# greenhousectrl-lab.net
KiCad netlist of a schematic drawn in EAGLE
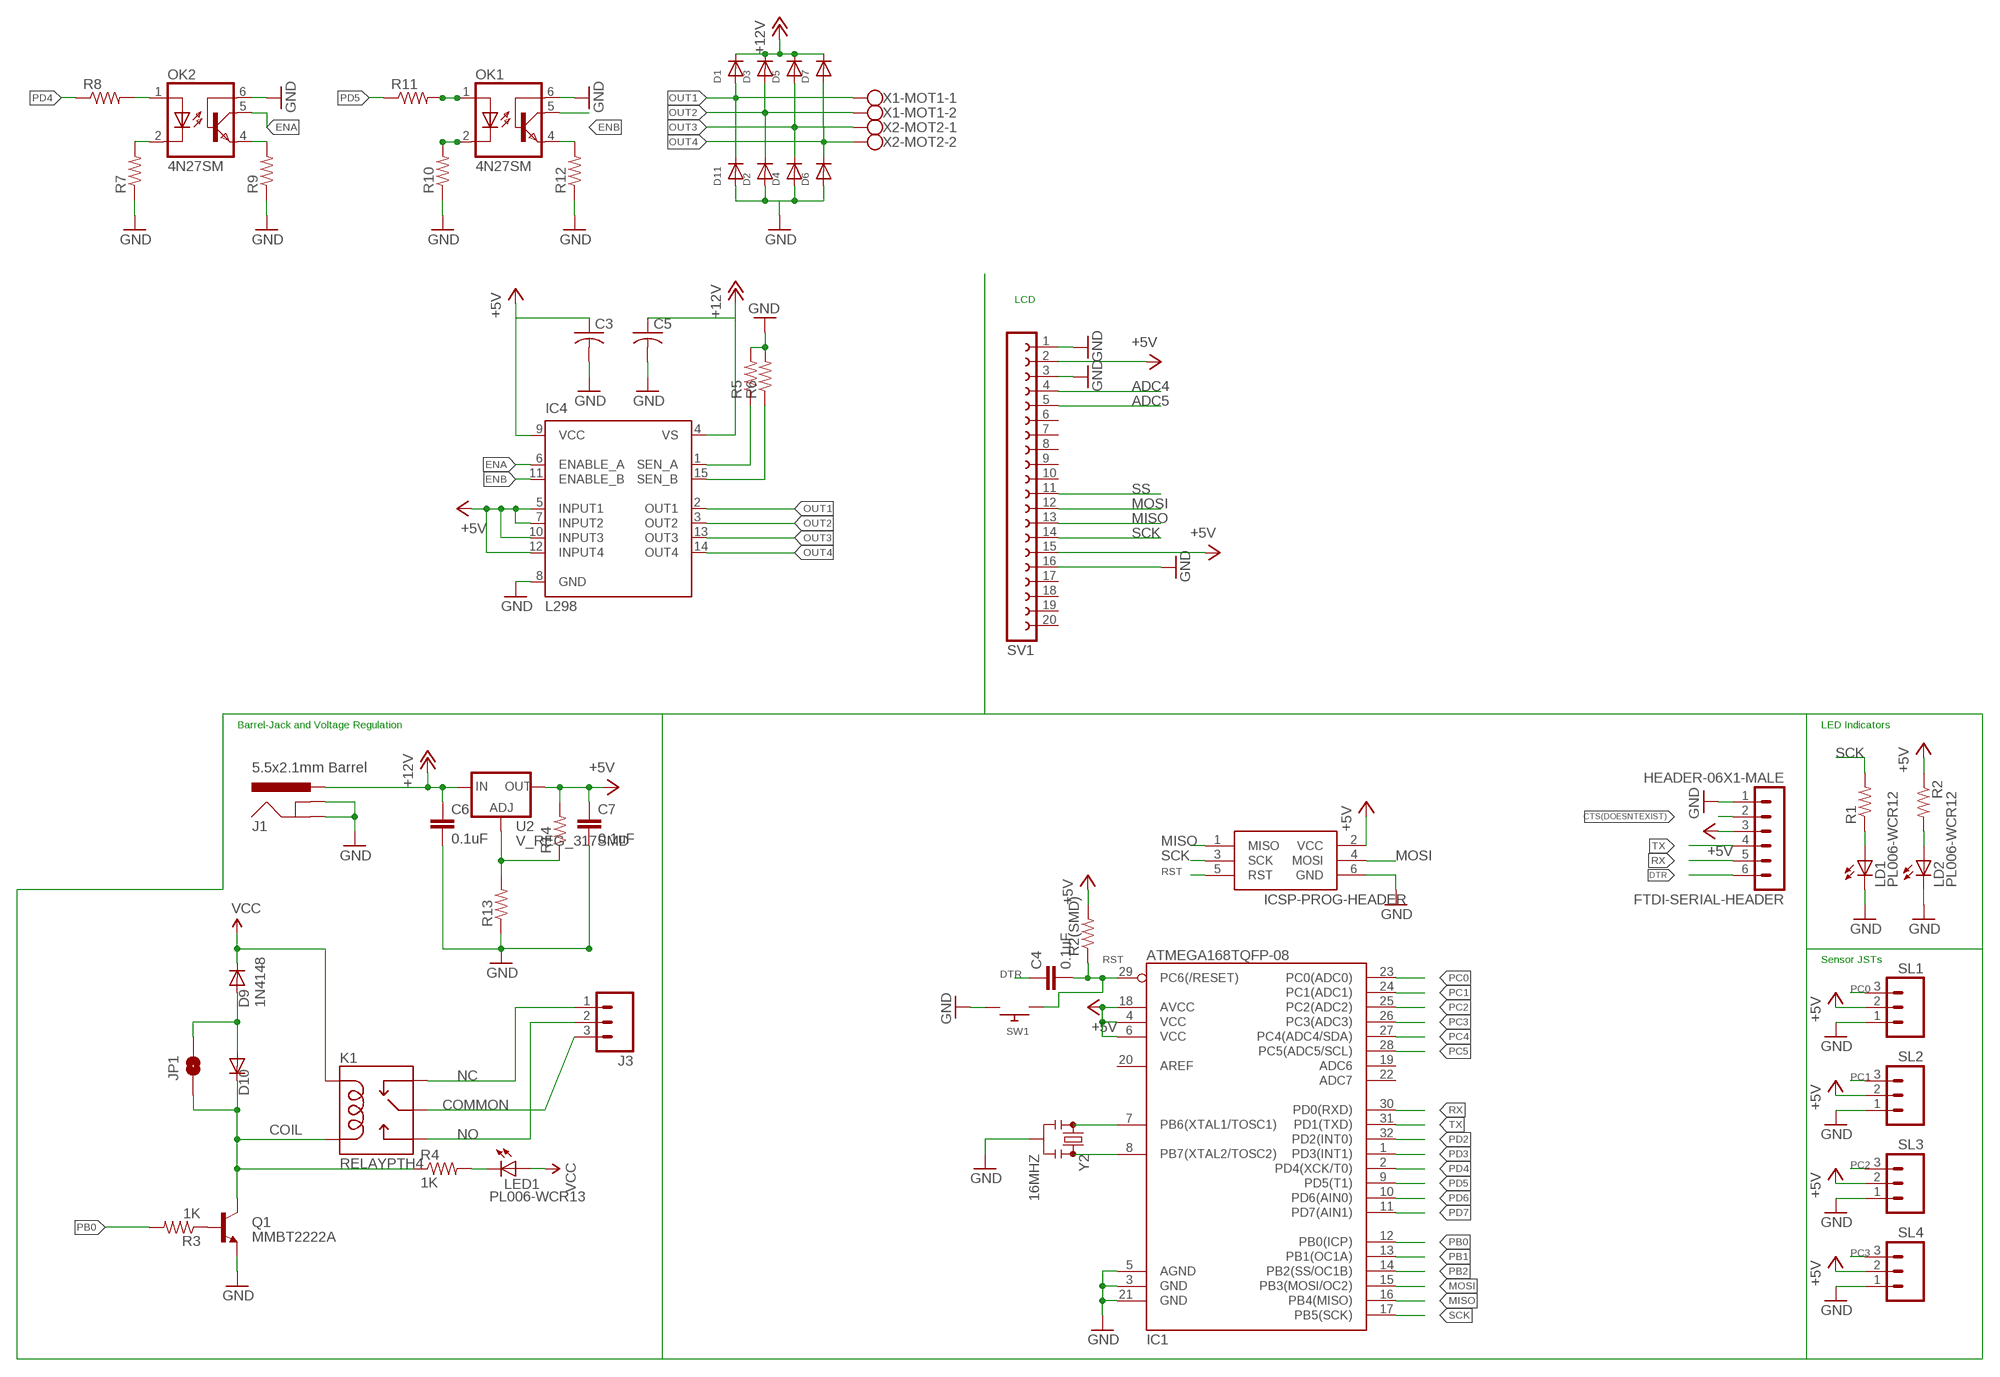
[diagram p0: schematic, sheet 1]

(export (version "E")
  (design (tool "Eeschema 10.0.6"))
  (components
    (comp (ref "C3")
      (value "C-US025-024X044")
      (footprint "eagle-import:C025-024X044")
      (libsource (lib "eagle-import") (part "C-US025-024X044"))
    )
    (comp (ref "C4")
      (value "0.1uF")
      (footprint "eagle-import:0603-CAP")
      (libsource (lib "eagle-import") (part "0.1UF-25V(+80/-20%)(0603)"))
    )
    (comp (ref "C5")
      (value "C-US025-024X044")
      (footprint "eagle-import:C025-024X044")
      (libsource (lib "eagle-import") (part "C-US025-024X044"))
    )
    (comp (ref "C6")
      (value "0.1uF")
      (footprint "eagle-import:0603-CAP")
      (libsource (lib "eagle-import") (part "0.1UF-25V(+80/-20%)(0603)"))
    )
    (comp (ref "C7")
      (value "0.1uF")
      (footprint "eagle-import:0603-CAP")
      (libsource (lib "eagle-import") (part "0.1UF-25V(+80/-20%)(0603)"))
    )
    (comp (ref "D1")
      (value "DIODESOD-523")
      (footprint "eagle-import:SOD-523")
      (libsource (lib "eagle-import") (part "DIODESOD-523"))
    )
    (comp (ref "D2")
      (value "DIODESOD-523")
      (footprint "eagle-import:SOD-523")
      (libsource (lib "eagle-import") (part "DIODESOD-523"))
    )
    (comp (ref "D3")
      (value "DIODESOD-523")
      (footprint "eagle-import:SOD-523")
      (libsource (lib "eagle-import") (part "DIODESOD-523"))
    )
    (comp (ref "D4")
      (value "DIODESOD-523")
      (footprint "eagle-import:SOD-523")
      (libsource (lib "eagle-import") (part "DIODESOD-523"))
    )
    (comp (ref "D5")
      (value "DIODESOD-523")
      (footprint "eagle-import:SOD-523")
      (libsource (lib "eagle-import") (part "DIODESOD-523"))
    )
    (comp (ref "D6")
      (value "DIODESOD-523")
      (footprint "eagle-import:SOD-523")
      (libsource (lib "eagle-import") (part "DIODESOD-523"))
    )
    (comp (ref "D7")
      (value "DIODESOD-523")
      (footprint "eagle-import:SOD-523")
      (libsource (lib "eagle-import") (part "DIODESOD-523"))
    )
    (comp (ref "D9")
      (value "1N4148")
      (footprint "eagle-import:SOD-323F")
      (libsource (lib "eagle-import") (part "DIODESOD-323F"))
    )
    (comp (ref "D10")
      (value "Zener")
      (footprint "eagle-import:SOD-323F")
      (libsource (lib "eagle-import") (part "DIODESOD-323F"))
    )
    (comp (ref "D11")
      (value "DIODESOD-523")
      (footprint "eagle-import:SOD-523")
      (libsource (lib "eagle-import") (part "DIODESOD-523"))
    )
    (comp (ref "FTDI-SERIAL-HEADER")
      (value "HEADER-06X1-MALE")
      (footprint "eagle-import:06X1-PTH")
      (libsource (lib "eagle-import") (part "HEADER-06X1?-MALE"))
    )
    (comp (ref "IC1")
      (value "ATMEGA168TQFP-08")
      (footprint "eagle-import:TQFP32-08")
      (libsource (lib "eagle-import") (part "ATMEGA168TQFP-08"))
    )
    (comp (ref "IC4")
      (value "L298")
      (footprint "eagle-import:MULTIWATT-15")
      (fields (field (name "MPN") "L298N"))
      (libsource (lib "eagle-import") (part "L298"))
    )
    (comp (ref "ICSP-PROG-HEADER")
      (value "AVRISP-6")
      (footprint "eagle-import:AVRISP")
      (libsource (lib "eagle-import") (part "AVRISP-6"))
    )
    (comp (ref "J1")
      (value "5.5x2.1mm Barrel")
      (footprint "eagle-import:POWER_JACK_SMD")
      (libsource (lib "eagle-import") (part "POWER_JACKSMD"))
    )
    (comp (ref "J3")
      (value "M03-SCREW-5MM")
      (footprint "eagle-import:SCREWTERMINAL-5MM-3")
      (libsource (lib "eagle-import") (part "M03-SCREW-5MM"))
    )
    (comp (ref "JP1")
      (value "JUMPER-PAD-2-NOYES_SILK")
      (footprint "eagle-import:PAD-JUMPER-2-NO_YES_SILK")
      (libsource (lib "eagle-import") (part "JUMPER-PAD-2-NOYES_SILK"))
    )
    (comp (ref "K1")
      (value "RELAYPTH4")
      (footprint "eagle-import:RELAY-JZC")
      (libsource (lib "eagle-import") (part "RELAYPTH4"))
    )
    (comp (ref "LD1")
      (value "PL006-WCR12")
      (footprint "eagle-import:SOT23")
      (libsource (lib "eagle-import") (part "PL006-WCR12"))
    )
    (comp (ref "LD2")
      (value "PL006-WCR12")
      (footprint "eagle-import:SOT23")
      (libsource (lib "eagle-import") (part "PL006-WCR12"))
    )
    (comp (ref "LED1")
      (value "PL006-WCR13")
      (footprint "eagle-import:SOT23")
      (fields (field (name "PROD_ID") "DIO-09529"))
      (libsource (lib "eagle-import") (part "PL006-WCR13"))
    )
    (comp (ref "OK1")
      (value "4N27SM")
      (footprint "eagle-import:DIL6-SMD")
      (fields (field (name "MF") "FAIRCHILD SEMICONDUCTOR") (field (name "MPN") "4N27S-M"))
      (libsource (lib "eagle-import") (part "4N?MS27"))
    )
    (comp (ref "OK2")
      (value "4N27SM")
      (footprint "eagle-import:DIL6-SMD")
      (fields (field (name "MF") "FAIRCHILD SEMICONDUCTOR") (field (name "MPN") "4N27S-M"))
      (libsource (lib "eagle-import") (part "4N?MS27"))
    )
    (comp (ref "Q1")
      (value "MMBT2222A")
      (footprint "eagle-import:SOT23-3")
      (libsource (lib "eagle-import") (part "TRANSISTOR_NPNMMBT2222A"))
    )
    (comp (ref "R1")
      (value "R-US_M0805")
      (footprint "eagle-import:M0805")
      (libsource (lib "eagle-import") (part "R-US_M0805"))
    )
    (comp (ref "R2")
      (value "R-US_M0805")
      (footprint "eagle-import:M0805")
      (libsource (lib "eagle-import") (part "R-US_M0805"))
    )
    (comp (ref "R2(SMD)")
      (value "R-US_M0805")
      (footprint "eagle-import:M0805")
      (libsource (lib "eagle-import") (part "R-US_M0805"))
    )
    (comp (ref "R3")
      (value "1K")
      (footprint "eagle-import:M0805")
      (libsource (lib "eagle-import") (part "R-US_M0805"))
    )
    (comp (ref "R4")
      (value "1K")
      (footprint "eagle-import:M0805")
      (libsource (lib "eagle-import") (part "R-US_M0805"))
    )
    (comp (ref "R5")
      (value "R-US_M0805")
      (footprint "eagle-import:M0805")
      (libsource (lib "eagle-import") (part "R-US_M0805"))
    )
    (comp (ref "R6")
      (value "R-US_M0805")
      (footprint "eagle-import:M0805")
      (libsource (lib "eagle-import") (part "R-US_M0805"))
    )
    (comp (ref "R7")
      (value "R-US_M0805")
      (footprint "eagle-import:M0805")
      (libsource (lib "eagle-import") (part "R-US_M0805"))
    )
    (comp (ref "R8")
      (value "R-US_M0805")
      (footprint "eagle-import:M0805")
      (libsource (lib "eagle-import") (part "R-US_M0805"))
    )
    (comp (ref "R9")
      (value "R-US_M0805")
      (footprint "eagle-import:M0805")
      (libsource (lib "eagle-import") (part "R-US_M0805"))
    )
    (comp (ref "R10")
      (value "R-US_M0805")
      (footprint "eagle-import:M0805")
      (libsource (lib "eagle-import") (part "R-US_M0805"))
    )
    (comp (ref "R11")
      (value "R-US_M0805")
      (footprint "eagle-import:M0805")
      (libsource (lib "eagle-import") (part "R-US_M0805"))
    )
    (comp (ref "R12")
      (value "R-US_M0805")
      (footprint "eagle-import:M0805")
      (libsource (lib "eagle-import") (part "R-US_M0805"))
    )
    (comp (ref "R13")
      (value "RESISTOR0402")
      (footprint "eagle-import:0402-RES")
      (libsource (lib "eagle-import") (part "RESISTOR0402"))
    )
    (comp (ref "R14")
      (value "RESISTOR0402")
      (footprint "eagle-import:0402-RES")
      (libsource (lib "eagle-import") (part "RESISTOR0402"))
    )
    (comp (ref "SL1")
      (value "M03")
      (footprint "eagle-import:03P")
      (libsource (lib "eagle-import") (part "M03"))
    )
    (comp (ref "SL2")
      (value "M03")
      (footprint "eagle-import:03P")
      (libsource (lib "eagle-import") (part "M03"))
    )
    (comp (ref "SL3")
      (value "M03")
      (footprint "eagle-import:03P")
      (libsource (lib "eagle-import") (part "M03"))
    )
    (comp (ref "SL4")
      (value "M03")
      (footprint "eagle-import:03P")
      (libsource (lib "eagle-import") (part "M03"))
    )
    (comp (ref "SV1")
      (value "FE20-1")
      (footprint "eagle-import:FE20")
      (libsource (lib "eagle-import") (part "FE20-1"))
    )
    (comp (ref "SW1")
      (value "SWITCH_PUSHBUTTONC&K_KSS")
      (footprint "eagle-import:BTN_CK_KSS")
      (libsource (lib "eagle-import") (part "SWITCH_PUSHBUTTONC&K_KSS"))
    )
    (comp (ref "U2")
      (value "V_REG_317SMD")
      (footprint "eagle-import:SOT223")
      (libsource (lib "eagle-import") (part "V_REG_317SMD"))
    )
    (comp (ref "X1-MOT1")
      (value "W237-102")
      (footprint "eagle-import:W237-102")
      (fields (field (name "MPN") "237-102"))
      (libsource (lib "eagle-import") (part "W237-102"))
    )
    (comp (ref "X2-MOT2")
      (value "W237-102")
      (footprint "eagle-import:W237-102")
      (fields (field (name "MPN") "237-102"))
      (libsource (lib "eagle-import") (part "W237-102"))
    )
    (comp (ref "Y2")
      (value "16MHZ")
      (footprint "eagle-import:RESONATOR-SMD")
      (libsource (lib "eagle-import") (part "RESONATOR16MHZ"))
    )
  )
  (nets
    (net (code "1") (name "+5V") (class "Default")
      (node (ref "C3") (pin "1") (pinfunction "1_1") (pintype "passive"))
      (node (ref "C7") (pin "1") (pinfunction "1_1") (pintype "passive"))
      (node (ref "FTDI-SERIAL-HEADER") (pin "3") (pinfunction "3_3") (pintype "passive"))
      (node (ref "IC1") (pin "18") (pinfunction "AVCC_18") (pintype "bidirectional"))
      (node (ref "IC1") (pin "4") (pinfunction "VCC_4") (pintype "bidirectional"))
      (node (ref "IC1") (pin "6") (pinfunction "VCC_6") (pintype "bidirectional"))
      (node (ref "IC4") (pin "10") (pinfunction "INPUT3_10") (pintype "input"))
      (node (ref "IC4") (pin "12") (pinfunction "INPUT4_12") (pintype "input"))
      (node (ref "IC4") (pin "5") (pinfunction "INPUT1_5") (pintype "input"))
      (node (ref "IC4") (pin "7") (pinfunction "INPUT2_7") (pintype "input"))
      (node (ref "IC4") (pin "9") (pinfunction "VCC_9") (pintype "power_in"))
      (node (ref "ICSP-PROG-HEADER") (pin "2") (pinfunction "VCC_2") (pintype "power_in"))
      (node (ref "R14") (pin "2") (pinfunction "2_2") (pintype "passive"))
      (node (ref "R2") (pin "1") (pinfunction "1_1") (pintype "passive"))
      (node (ref "R2(SMD)") (pin "2") (pinfunction "2_2") (pintype "passive"))
      (node (ref "SL1") (pin "2") (pinfunction "2_2") (pintype "passive"))
      (node (ref "SL2") (pin "2") (pinfunction "2_2") (pintype "passive"))
      (node (ref "SL3") (pin "2") (pinfunction "2_2") (pintype "passive"))
      (node (ref "SL4") (pin "2") (pinfunction "2_2") (pintype "passive"))
      (node (ref "SV1") (pin "15") (pinfunction "15_15") (pintype "passive"))
      (node (ref "SV1") (pin "2") (pinfunction "2_2") (pintype "passive"))
      (node (ref "U2") (pin "2") (pinfunction "OUT_2") (pintype "output"))
    )
    (net (code "2") (name "+12V") (class "Default")
      (node (ref "C5") (pin "1") (pinfunction "1_1") (pintype "passive"))
      (node (ref "C6") (pin "1") (pinfunction "1_1") (pintype "passive"))
      (node (ref "D1") (pin "K") (pinfunction "C_K") (pintype "passive"))
      (node (ref "D3") (pin "K") (pinfunction "C_K") (pintype "passive"))
      (node (ref "D5") (pin "K") (pinfunction "C_K") (pintype "passive"))
      (node (ref "D7") (pin "K") (pinfunction "C_K") (pintype "passive"))
      (node (ref "IC4") (pin "4") (pinfunction "VS_4") (pintype "power_in"))
      (node (ref "J1") (pin "VIN0") (pinfunction "PWR_VIN0") (pintype "bidirectional"))
      (node (ref "U2") (pin "3") (pinfunction "IN_3") (pintype "input"))
    )
    (net (code "3") (name "/ADC4") (class "Default")
      (node (ref "SV1") (pin "4") (pinfunction "4_4") (pintype "passive"))
    )
    (net (code "4") (name "/ADC5") (class "Default")
      (node (ref "SV1") (pin "5") (pinfunction "5_5") (pintype "passive"))
    )
    (net (code "5") (name "/COIL") (class "Default")
      (node (ref "D10") (pin "C") (pinfunction "C_C") (pintype "passive"))
      (node (ref "JP1") (pin "1") (pinfunction "1_1") (pintype "passive"))
      (node (ref "K1") (pin "1") (pinfunction "COIL2_1") (pintype "bidirectional"))
      (node (ref "Q1") (pin "3") (pinfunction "C_3") (pintype "passive"))
      (node (ref "R4") (pin "1") (pinfunction "1_1") (pintype "passive"))
    )
    (net (code "6") (name "/COMMON") (class "Default")
      (node (ref "J3") (pin "3") (pinfunction "3_3") (pintype "passive"))
      (node (ref "K1") (pin "4") (pinfunction "MAIN_4") (pintype "bidirectional"))
    )
    (net (code "7") (name "/NC") (class "Default")
      (node (ref "J3") (pin "1") (pinfunction "1_1") (pintype "passive"))
      (node (ref "K1") (pin "2") (pinfunction "NC_2") (pintype "bidirectional"))
    )
    (net (code "8") (name "/NO") (class "Default")
      (node (ref "J3") (pin "2") (pinfunction "2_2") (pintype "passive"))
      (node (ref "K1") (pin "3") (pinfunction "NO_3") (pintype "bidirectional"))
    )
    (net (code "9") (name "/RST") (class "Default")
      (node (ref "C4") (pin "2") (pinfunction "2_2") (pintype "passive"))
      (node (ref "IC1") (pin "29") (pinfunction "PC6(/RESET)_29") (pintype "bidirectional"))
      (node (ref "ICSP-PROG-HEADER") (pin "5") (pinfunction "RST_5") (pintype "output"))
      (node (ref "R2(SMD)") (pin "1") (pinfunction "1_1") (pintype "passive"))
      (node (ref "SW1") (pin "P$1") (pinfunction "P$1_P$1") (pintype "passive"))
    )
    (net (code "10") (name "/SS") (class "Default")
      (node (ref "SV1") (pin "11") (pinfunction "11_11") (pintype "passive"))
    )
    (net (code "11") (name "CTS(DOESNTEXIST)") (class "Default")
      (node (ref "FTDI-SERIAL-HEADER") (pin "2") (pinfunction "2_2") (pintype "passive"))
    )
    (net (code "12") (name "DTR") (class "Default")
      (node (ref "C4") (pin "1") (pinfunction "1_1") (pintype "passive"))
      (node (ref "FTDI-SERIAL-HEADER") (pin "6") (pinfunction "6_6") (pintype "passive"))
    )
    (net (code "13") (name "ENA") (class "Default")
      (node (ref "IC4") (pin "6") (pinfunction "ENABLE_A_6") (pintype "input"))
      (node (ref "OK2") (pin "5") (pinfunction "COL_5") (pintype "passive"))
    )
    (net (code "14") (name "ENB") (class "Default")
      (node (ref "IC4") (pin "11") (pinfunction "ENABLE_B_11") (pintype "input"))
      (node (ref "OK1") (pin "5") (pinfunction "COL_5") (pintype "passive"))
    )
    (net (code "15") (name "GND") (class "Default")
      (node (ref "C3") (pin "2") (pinfunction "2_2") (pintype "passive"))
      (node (ref "C5") (pin "2") (pinfunction "2_2") (pintype "passive"))
      (node (ref "C6") (pin "2") (pinfunction "2_2") (pintype "passive"))
      (node (ref "C7") (pin "2") (pinfunction "2_2") (pintype "passive"))
      (node (ref "D11") (pin "A") (pinfunction "A_A") (pintype "passive"))
      (node (ref "D2") (pin "A") (pinfunction "A_A") (pintype "passive"))
      (node (ref "D4") (pin "A") (pinfunction "A_A") (pintype "passive"))
      (node (ref "D6") (pin "A") (pinfunction "A_A") (pintype "passive"))
      (node (ref "FTDI-SERIAL-HEADER") (pin "1") (pinfunction "1_1") (pintype "passive"))
      (node (ref "IC1") (pin "21") (pinfunction "GND_21") (pintype "bidirectional"))
      (node (ref "IC1") (pin "3") (pinfunction "GND_3") (pintype "bidirectional"))
      (node (ref "IC1") (pin "5") (pinfunction "AGND_5") (pintype "bidirectional"))
      (node (ref "IC4") (pin "8") (pinfunction "GND_8") (pintype "power_in"))
      (node (ref "ICSP-PROG-HEADER") (pin "6") (pinfunction "GND_6") (pintype "power_in"))
      (node (ref "J1") (pin "GND") (pinfunction "GNDBREAK_GND") (pintype "bidirectional"))
      (node (ref "J1") (pin "P$4") (pinfunction "GND_P$4") (pintype "bidirectional"))
      (node (ref "LD1") (pin "3") (pinfunction "C_3") (pintype "passive"))
      (node (ref "LD2") (pin "3") (pinfunction "C_3") (pintype "passive"))
      (node (ref "OK1") (pin "6") (pinfunction "BAS_6") (pintype "passive"))
      (node (ref "OK2") (pin "6") (pinfunction "BAS_6") (pintype "passive"))
      (node (ref "Q1") (pin "2") (pinfunction "E_2") (pintype "passive"))
      (node (ref "R10") (pin "1") (pinfunction "1_1") (pintype "passive"))
      (node (ref "R12") (pin "1") (pinfunction "1_1") (pintype "passive"))
      (node (ref "R13") (pin "1") (pinfunction "1_1") (pintype "passive"))
      (node (ref "R5") (pin "2") (pinfunction "2_2") (pintype "passive"))
      (node (ref "R6") (pin "2") (pinfunction "2_2") (pintype "passive"))
      (node (ref "R7") (pin "1") (pinfunction "1_1") (pintype "passive"))
      (node (ref "R9") (pin "1") (pinfunction "1_1") (pintype "passive"))
      (node (ref "SL1") (pin "1") (pinfunction "1_1") (pintype "passive"))
      (node (ref "SL2") (pin "1") (pinfunction "1_1") (pintype "passive"))
      (node (ref "SL3") (pin "1") (pinfunction "1_1") (pintype "passive"))
      (node (ref "SL4") (pin "1") (pinfunction "1_1") (pintype "passive"))
      (node (ref "SV1") (pin "1") (pinfunction "1_1") (pintype "passive"))
      (node (ref "SV1") (pin "16") (pinfunction "16_16") (pintype "passive"))
      (node (ref "SV1") (pin "3") (pinfunction "3_3") (pintype "passive"))
      (node (ref "SW1") (pin "P$2") (pinfunction "P$2_P$2") (pintype "passive"))
      (node (ref "Y2") (pin "2") (pinfunction "2_2") (pintype "passive"))
    )
    (net (code "16") (name "MISO") (class "Default")
      (node (ref "IC1") (pin "16") (pinfunction "PB4(MISO)_16") (pintype "bidirectional"))
      (node (ref "ICSP-PROG-HEADER") (pin "1") (pinfunction "MISO_1") (pintype "input"))
      (node (ref "SV1") (pin "13") (pinfunction "13_13") (pintype "passive"))
    )
    (net (code "17") (name "MOSI") (class "Default")
      (node (ref "IC1") (pin "15") (pinfunction "PB3(MOSI/OC2)_15") (pintype "bidirectional"))
      (node (ref "ICSP-PROG-HEADER") (pin "4") (pinfunction "MOSI_4") (pintype "output"))
      (node (ref "SV1") (pin "12") (pinfunction "12_12") (pintype "passive"))
    )
    (net (code "18") (name "Net-(D10-PadA)") (class "Default")
      (node (ref "D10") (pin "A") (pinfunction "A_A") (pintype "passive"))
      (node (ref "D9") (pin "A") (pinfunction "A_A") (pintype "passive"))
      (node (ref "JP1") (pin "2") (pinfunction "2_2") (pintype "passive"))
    )
    (net (code "19") (name "Net-(IC1-PB6(XTAL1{slash}TOSC1))") (class "Default")
      (node (ref "IC1") (pin "7") (pinfunction "PB6(XTAL1/TOSC1)_7") (pintype "bidirectional"))
      (node (ref "Y2") (pin "1") (pinfunction "1_1") (pintype "passive"))
    )
    (net (code "20") (name "Net-(IC1-PB7(XTAL2{slash}TOSC2))") (class "Default")
      (node (ref "IC1") (pin "8") (pinfunction "PB7(XTAL2/TOSC2)_8") (pintype "bidirectional"))
      (node (ref "Y2") (pin "3") (pinfunction "3_3") (pintype "passive"))
    )
    (net (code "21") (name "Net-(IC4-SEN_A)") (class "Default")
      (node (ref "IC4") (pin "1") (pinfunction "SEN_A_1") (pintype "input"))
      (node (ref "R5") (pin "1") (pinfunction "1_1") (pintype "passive"))
    )
    (net (code "22") (name "Net-(IC4-SEN_B)") (class "Default")
      (node (ref "IC4") (pin "15") (pinfunction "SEN_B_15") (pintype "input"))
      (node (ref "R6") (pin "1") (pinfunction "1_1") (pintype "passive"))
    )
    (net (code "23") (name "Net-(LD1-A)") (class "Default")
      (node (ref "LD1") (pin "1") (pinfunction "A_1") (pintype "passive"))
      (node (ref "R1") (pin "1") (pinfunction "1_1") (pintype "passive"))
    )
    (net (code "24") (name "Net-(LD2-A)") (class "Default")
      (node (ref "LD2") (pin "1") (pinfunction "A_1") (pintype "passive"))
      (node (ref "R2") (pin "2") (pinfunction "2_2") (pintype "passive"))
    )
    (net (code "25") (name "Net-(LED1-C)") (class "Default")
      (node (ref "LED1") (pin "3") (pinfunction "C_3") (pintype "passive"))
      (node (ref "R4") (pin "2") (pinfunction "2_2") (pintype "passive"))
    )
    (net (code "26") (name "Net-(OK1-A)") (class "Default")
      (node (ref "OK1") (pin "1") (pinfunction "A_1") (pintype "passive"))
      (node (ref "R11") (pin "2") (pinfunction "2_2") (pintype "passive"))
    )
    (net (code "27") (name "Net-(OK1-C)") (class "Default")
      (node (ref "OK1") (pin "2") (pinfunction "C_2") (pintype "passive"))
      (node (ref "R10") (pin "2") (pinfunction "2_2") (pintype "passive"))
    )
    (net (code "28") (name "Net-(OK1-EMI)") (class "Default")
      (node (ref "OK1") (pin "4") (pinfunction "EMI_4") (pintype "passive"))
      (node (ref "R12") (pin "2") (pinfunction "2_2") (pintype "passive"))
    )
    (net (code "29") (name "Net-(OK2-A)") (class "Default")
      (node (ref "OK2") (pin "1") (pinfunction "A_1") (pintype "passive"))
      (node (ref "R8") (pin "2") (pinfunction "2_2") (pintype "passive"))
    )
    (net (code "30") (name "Net-(OK2-C)") (class "Default")
      (node (ref "OK2") (pin "2") (pinfunction "C_2") (pintype "passive"))
      (node (ref "R7") (pin "2") (pinfunction "2_2") (pintype "passive"))
    )
    (net (code "31") (name "Net-(OK2-EMI)") (class "Default")
      (node (ref "OK2") (pin "4") (pinfunction "EMI_4") (pintype "passive"))
      (node (ref "R9") (pin "2") (pinfunction "2_2") (pintype "passive"))
    )
    (net (code "32") (name "Net-(Q1-B)") (class "Default")
      (node (ref "Q1") (pin "1") (pinfunction "B_1") (pintype "passive"))
      (node (ref "R3") (pin "1") (pinfunction "1_1") (pintype "passive"))
    )
    (net (code "33") (name "Net-(U2-ADJ)") (class "Default")
      (node (ref "R13") (pin "2") (pinfunction "2_2") (pintype "passive"))
      (node (ref "R14") (pin "1") (pinfunction "1_1") (pintype "passive"))
      (node (ref "U2") (pin "1") (pinfunction "ADJ_1") (pintype "input"))
    )
    (net (code "34") (name "OUT1") (class "Default")
      (node (ref "D1") (pin "A") (pinfunction "A_A") (pintype "passive"))
      (node (ref "D11") (pin "K") (pinfunction "C_K") (pintype "passive"))
      (node (ref "IC4") (pin "2") (pinfunction "OUT1_2") (pintype "output"))
      (node (ref "X1-MOT1") (pin "1") (pinfunction "KL_1") (pintype "passive"))
    )
    (net (code "35") (name "OUT2") (class "Default")
      (node (ref "D2") (pin "K") (pinfunction "C_K") (pintype "passive"))
      (node (ref "D3") (pin "A") (pinfunction "A_A") (pintype "passive"))
      (node (ref "IC4") (pin "3") (pinfunction "OUT2_3") (pintype "output"))
      (node (ref "X1-MOT1") (pin "2") (pinfunction "KL_2") (pintype "passive"))
    )
    (net (code "36") (name "OUT3") (class "Default")
      (node (ref "D4") (pin "K") (pinfunction "C_K") (pintype "passive"))
      (node (ref "D5") (pin "A") (pinfunction "A_A") (pintype "passive"))
      (node (ref "IC4") (pin "13") (pinfunction "OUT3_13") (pintype "output"))
      (node (ref "X2-MOT2") (pin "1") (pinfunction "KL_1") (pintype "passive"))
    )
    (net (code "37") (name "OUT4") (class "Default")
      (node (ref "D6") (pin "K") (pinfunction "C_K") (pintype "passive"))
      (node (ref "D7") (pin "A") (pinfunction "A_A") (pintype "passive"))
      (node (ref "IC4") (pin "14") (pinfunction "OUT4_14") (pintype "output"))
      (node (ref "X2-MOT2") (pin "2") (pinfunction "KL_2") (pintype "passive"))
    )
    (net (code "38") (name "PB0") (class "Default")
      (node (ref "IC1") (pin "12") (pinfunction "PB0(ICP)_12") (pintype "bidirectional"))
      (node (ref "R3") (pin "2") (pinfunction "2_2") (pintype "passive"))
    )
    (net (code "39") (name "PB1") (class "Default")
      (node (ref "IC1") (pin "13") (pinfunction "PB1(OC1A)_13") (pintype "bidirectional"))
    )
    (net (code "40") (name "PB2") (class "Default")
      (node (ref "IC1") (pin "14") (pinfunction "PB2(SS/OC1B)_14") (pintype "bidirectional"))
    )
    (net (code "41") (name "PC0") (class "Default")
      (node (ref "IC1") (pin "23") (pinfunction "PC0(ADC0)_23") (pintype "bidirectional"))
      (node (ref "SL1") (pin "3") (pinfunction "3_3") (pintype "passive"))
    )
    (net (code "42") (name "PC1") (class "Default")
      (node (ref "IC1") (pin "24") (pinfunction "PC1(ADC1)_24") (pintype "bidirectional"))
      (node (ref "SL2") (pin "3") (pinfunction "3_3") (pintype "passive"))
    )
    (net (code "43") (name "PC2") (class "Default")
      (node (ref "IC1") (pin "25") (pinfunction "PC2(ADC2)_25") (pintype "bidirectional"))
      (node (ref "SL3") (pin "3") (pinfunction "3_3") (pintype "passive"))
    )
    (net (code "44") (name "PC3") (class "Default")
      (node (ref "IC1") (pin "26") (pinfunction "PC3(ADC3)_26") (pintype "bidirectional"))
      (node (ref "SL4") (pin "3") (pinfunction "3_3") (pintype "passive"))
    )
    (net (code "45") (name "PC4") (class "Default")
      (node (ref "IC1") (pin "27") (pinfunction "PC4(ADC4/SDA)_27") (pintype "bidirectional"))
    )
    (net (code "46") (name "PC5") (class "Default")
      (node (ref "IC1") (pin "28") (pinfunction "PC5(ADC5/SCL)_28") (pintype "bidirectional"))
    )
    (net (code "47") (name "PD2") (class "Default")
      (node (ref "IC1") (pin "32") (pinfunction "PD2(INT0)_32") (pintype "bidirectional"))
    )
    (net (code "48") (name "PD3") (class "Default")
      (node (ref "IC1") (pin "1") (pinfunction "PD3(INT1)_1") (pintype "bidirectional"))
    )
    (net (code "49") (name "PD4") (class "Default")
      (node (ref "IC1") (pin "2") (pinfunction "PD4(XCK/T0)_2") (pintype "bidirectional"))
      (node (ref "R8") (pin "1") (pinfunction "1_1") (pintype "passive"))
    )
    (net (code "50") (name "PD5") (class "Default")
      (node (ref "IC1") (pin "9") (pinfunction "PD5(T1)_9") (pintype "bidirectional"))
      (node (ref "R11") (pin "1") (pinfunction "1_1") (pintype "passive"))
    )
    (net (code "51") (name "PD6") (class "Default")
      (node (ref "IC1") (pin "10") (pinfunction "PD6(AIN0)_10") (pintype "bidirectional"))
    )
    (net (code "52") (name "PD7") (class "Default")
      (node (ref "IC1") (pin "11") (pinfunction "PD7(AIN1)_11") (pintype "bidirectional"))
    )
    (net (code "53") (name "RX") (class "Default")
      (node (ref "FTDI-SERIAL-HEADER") (pin "5") (pinfunction "5_5") (pintype "passive"))
      (node (ref "IC1") (pin "30") (pinfunction "PD0(RXD)_30") (pintype "bidirectional"))
    )
    (net (code "54") (name "SCK") (class "Default")
      (node (ref "IC1") (pin "17") (pinfunction "PB5(SCK)_17") (pintype "bidirectional"))
      (node (ref "ICSP-PROG-HEADER") (pin "3") (pinfunction "SCK_3") (pintype "output"))
      (node (ref "R1") (pin "2") (pinfunction "2_2") (pintype "passive"))
      (node (ref "SV1") (pin "14") (pinfunction "14_14") (pintype "passive"))
    )
    (net (code "55") (name "TX") (class "Default")
      (node (ref "FTDI-SERIAL-HEADER") (pin "4") (pinfunction "4_4") (pintype "passive"))
      (node (ref "IC1") (pin "31") (pinfunction "PD1(TXD)_31") (pintype "bidirectional"))
    )
    (net (code "56") (name "VCC") (class "Default")
      (node (ref "D9") (pin "C") (pinfunction "C_C") (pintype "passive"))
      (node (ref "K1") (pin "5") (pinfunction "COIL1_5") (pintype "bidirectional"))
      (node (ref "LED1") (pin "1") (pinfunction "A_1") (pintype "passive"))
    )
    (net (code "57") (name "unconnected-(IC1-ADC6-Pad19)") (class "Default")
      (node (ref "IC1") (pin "19") (pinfunction "ADC6_19") (pintype "bidirectional"))
    )
    (net (code "58") (name "unconnected-(IC1-ADC7-Pad22)") (class "Default")
      (node (ref "IC1") (pin "22") (pinfunction "ADC7_22") (pintype "bidirectional"))
    )
    (net (code "59") (name "unconnected-(IC1-AREF-Pad20)") (class "Default")
      (node (ref "IC1") (pin "20") (pinfunction "AREF_20") (pintype "bidirectional"))
    )
    (net (code "60") (name "unconnected-(SV1-Pad6)") (class "Default")
      (node (ref "SV1") (pin "6") (pinfunction "6_6") (pintype "passive"))
    )
    (net (code "61") (name "unconnected-(SV1-Pad7)") (class "Default")
      (node (ref "SV1") (pin "7") (pinfunction "7_7") (pintype "passive"))
    )
    (net (code "62") (name "unconnected-(SV1-Pad8)") (class "Default")
      (node (ref "SV1") (pin "8") (pinfunction "8_8") (pintype "passive"))
    )
    (net (code "63") (name "unconnected-(SV1-Pad9)") (class "Default")
      (node (ref "SV1") (pin "9") (pinfunction "9_9") (pintype "passive"))
    )
    (net (code "64") (name "unconnected-(SV1-Pad10)") (class "Default")
      (node (ref "SV1") (pin "10") (pinfunction "10_10") (pintype "passive"))
    )
    (net (code "65") (name "unconnected-(SV1-Pad17)") (class "Default")
      (node (ref "SV1") (pin "17") (pinfunction "17_17") (pintype "passive"))
    )
    (net (code "66") (name "unconnected-(SV1-Pad18)") (class "Default")
      (node (ref "SV1") (pin "18") (pinfunction "18_18") (pintype "passive"))
    )
    (net (code "67") (name "unconnected-(SV1-Pad19)") (class "Default")
      (node (ref "SV1") (pin "19") (pinfunction "19_19") (pintype "passive"))
    )
    (net (code "68") (name "unconnected-(SV1-Pad20)") (class "Default")
      (node (ref "SV1") (pin "20") (pinfunction "20_20") (pintype "passive"))
    )
  )
)
